# 01_Power.net
KiCad netlist of a schematic drawn in Altium Designer
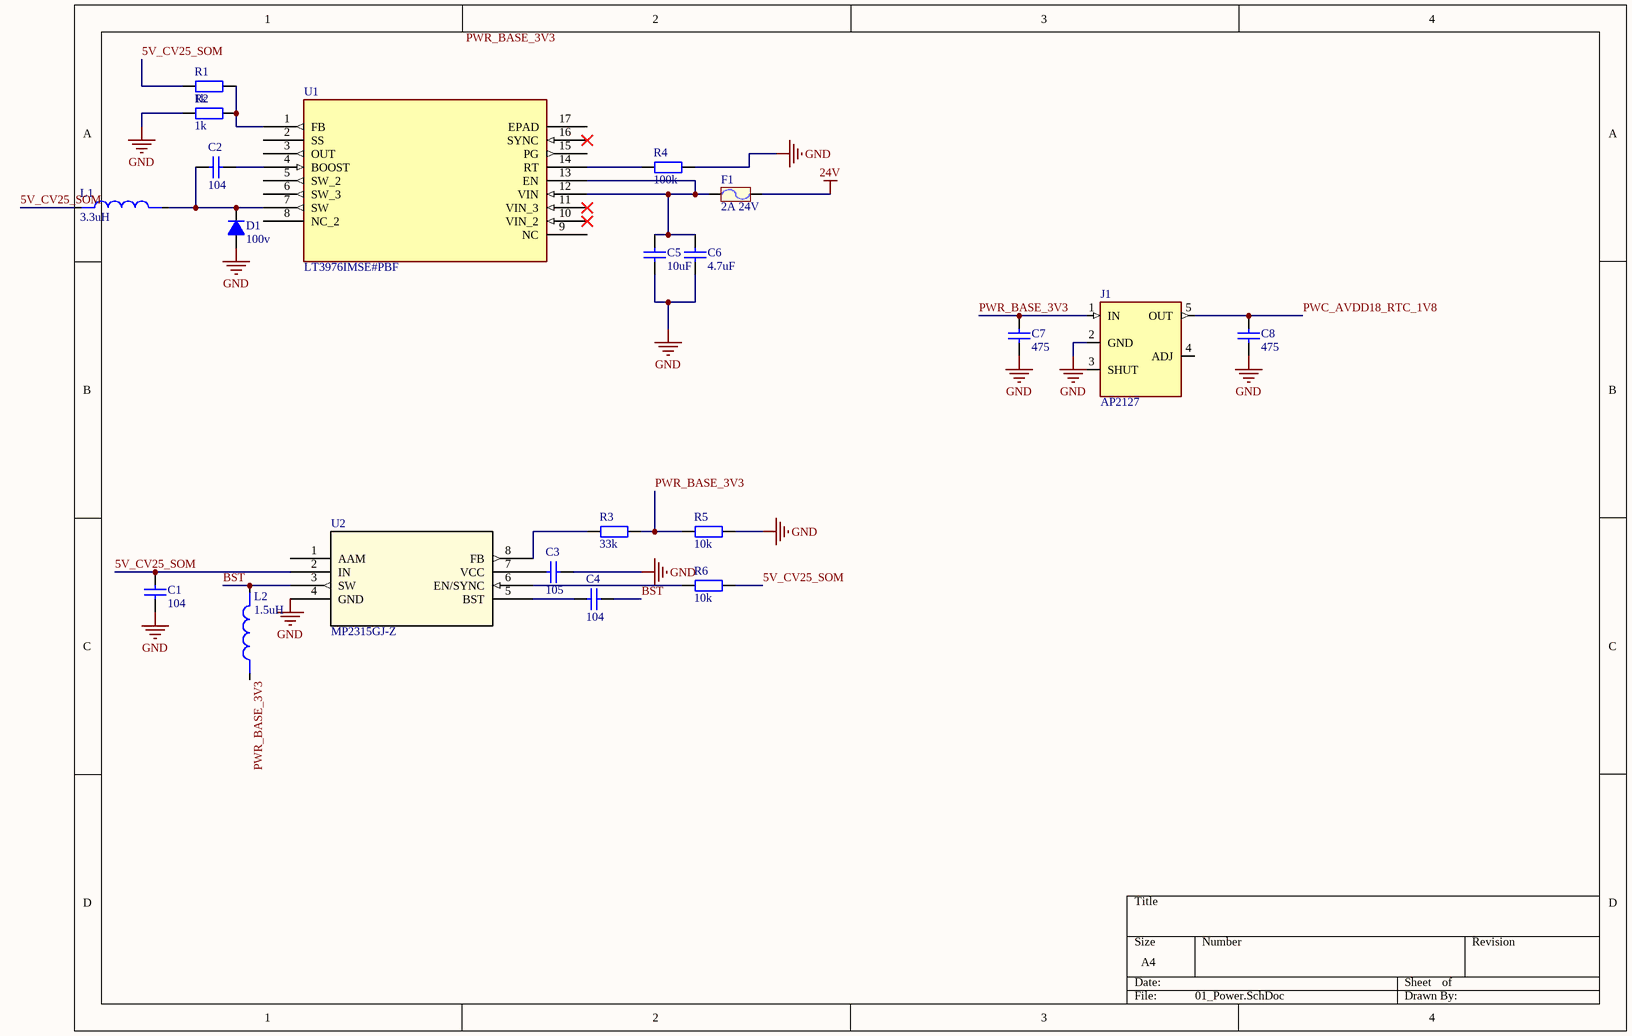
[diagram p0: 01_Power.SchDoc]

(export (version "E")
  (design (tool "Eeschema 10.0.6"))
  (components
    (comp (ref "C1")
      (value "104")
      (footprint "tu 0603")
      (description "Dán")
      (libsource (lib "Altium_Lib_by_KhueNguyenCreator") (part "Tu 0603 104 50V 10%"))
    )
    (comp (ref "C2")
      (value "104")
      (footprint "tu 0603")
      (description "Dán")
      (libsource (lib "Altium_Lib_by_KhueNguyenCreator") (part "Tu 0603 104 50V 10%"))
    )
    (comp (ref "C3")
      (value "105")
      (footprint "tu 0603")
      (description "Dán")
      (libsource (lib "Altium_Lib_by_KhueNguyenCreator") (part "Tu 0603 105 16V 20%"))
    )
    (comp (ref "C4")
      (value "104")
      (footprint "tu 0603")
      (description "Dán")
      (libsource (lib "Altium_Lib_by_KhueNguyenCreator") (part "Tu 0603 104 50V 10%"))
    )
    (comp (ref "C5")
      (value "10uF")
      (footprint "tu 0603")
      (description "Dán")
      (libsource (lib "Altium_Lib_by_KhueNguyenCreator") (part "Tu 0603 470pF 50V 10%"))
    )
    (comp (ref "C6")
      (value "4.7uF")
      (footprint "tu 0603")
      (description "Dán")
      (libsource (lib "Altium_Lib_by_KhueNguyenCreator") (part "Tu 0603 470pF 50V 10%"))
    )
    (comp (ref "C7")
      (value "475")
      (footprint "tu 0805")
      (description "Dán")
      (libsource (lib "Altium_Lib_by_KhueNguyenCreator") (part "Tu 0805 475 25V 20%"))
    )
    (comp (ref "C8")
      (value "475")
      (footprint "tu 0805")
      (description "Dán")
      (libsource (lib "Altium_Lib_by_KhueNguyenCreator") (part "Tu 0805 475 25V 20%"))
    )
    (comp (ref "D1")
      (value "100v")
      (footprint "DIODE 1A")
      (description "Cắm")
      (libsource (lib "Altium_Lib_by_KhueNguyenCreator") (part "Diode 1N4007"))
    )
    (comp (ref "F1")
      (value "2A 24V")
      (footprint "Cau chi tu phuc hoi 2A 24V SMD1812")
      (description "2A 24V SMD1812")
      (libsource (lib "Altium_Lib_by_KhueNguyenCreator") (part "Cau chi tu phuc hoi 2A 24V SMD1812"))
    )
    (comp (ref "J1")
      (value "AP2127")
      (footprint "AP2127K-3.3")
      (description "LDO Regulator Pos 1.8V 0.4A 5-Pin SOT-23 T/R / IC REG LDO 1.8V 0.3A SOT23-5")
      (fields (field (name "MF") "Diodes Incorporated"))
      (libsource (lib "AP2127") (part "AP2127"))
    )
    (comp (ref "L1")
      (value "3.3uH")
      (footprint "CUON CAM SMD 0530")
      (description "SMD 0530")
      (fields (field (name "MP") "FDV0530-H-1R5M=P3"))
      (libsource (lib "Altium_Lib_by_KhueNguyenCreator") (part "Cuon Cam SMD 0530"))
    )
    (comp (ref "L2")
      (value "1.5uH")
      (footprint "CUON CAM SMD 0530")
      (description "SMD 0530")
      (fields (field (name "MP") "FDV0530-H-1R5M=P3"))
      (libsource (lib "Altium_Lib_by_KhueNguyenCreator") (part "Cuon Cam SMD 0530"))
    )
    (comp (ref "R1")
      (value "1k")
      (footprint "tro smd 0603")
      (description "Dán")
      (libsource (lib "Altium_Lib_by_KhueNguyenCreator") (part "Tro 0603 1% 1k"))
    )
    (comp (ref "R2")
      (value "1k")
      (footprint "tro smd 0603")
      (description "Dán")
      (libsource (lib "Altium_Lib_by_KhueNguyenCreator") (part "Tro 0603 1% 1k"))
    )
    (comp (ref "R3")
      (value "33k")
      (footprint "Tro smd 0603")
      (description "Dán")
      (libsource (lib "Altium_Lib_by_KhueNguyenCreator") (part "Tro 0603 1% 33k"))
    )
    (comp (ref "R4")
      (value "100k")
      (footprint "tro smd 0805")
      (description "Dán")
      (libsource (lib "Altium_Lib_by_KhueNguyenCreator") (part "Tro 0805 5% 100k"))
    )
    (comp (ref "R5")
      (value "10k")
      (footprint "tro smd 0603")
      (description "Dán")
      (libsource (lib "Altium_Lib_by_KhueNguyenCreator") (part "Tro 0603 1% 10k"))
    )
    (comp (ref "R6")
      (value "10k")
      (footprint "tro smd 0603")
      (description "Dán")
      (libsource (lib "Altium_Lib_by_KhueNguyenCreator") (part "Tro 0603 1% 10k"))
    )
    (comp (ref "U1")
      (value "LT3976IMSE#PBF")
      (footprint "MSOP-16_MSE")
      (description "40V, 5A, 2MHz Step-Down Switching Regulator with 3.3渭A Quiescent Current")
      (fields (field (name "MF") "Analog Devices"))
      (libsource (lib "LT3976IMSE_PBF") (part "LT3976IMSE#PBF"))
    )
    (comp (ref "U2")
      (value "MP2315GJ-Z")
      (footprint "TSOT23-8_MPS")
      (fields (field (name "COPYRIGHT") "Copyright (C) 2026 Ultra Librarian. All rights reserved."))
      (libsource (lib "MP2315GJ-Z") (part "MP2315GJ-Z"))
    )
  )
  (nets
    (net (code "1") (name "/5V_CV25_SOM") (class "Default")
      (node (ref "C1") (pin "1") (pinfunction "1_1") (pintype "passive"))
      (node (ref "L1") (pin "1") (pinfunction "1_1") (pintype "passive"))
      (node (ref "R1") (pin "1") (pinfunction "1_1") (pintype "passive"))
      (node (ref "R6") (pin "2") (pinfunction "2_2") (pintype "passive"))
      (node (ref "U2") (pin "2") (pinfunction "IN_2") (pintype "power_in"))
    )
    (net (code "2") (name "/BST") (class "Default")
      (node (ref "C4") (pin "1") (pinfunction "1_1") (pintype "passive"))
      (node (ref "L2") (pin "2") (pinfunction "2_2") (pintype "passive"))
      (node (ref "U2") (pin "3") (pinfunction "SW_3") (pintype "output"))
    )
    (net (code "3") (name "/PWC_AVDD18_RTC_1V8") (class "Default")
      (node (ref "C8") (pin "1") (pinfunction "1_1") (pintype "passive"))
      (node (ref "J1") (pin "5") (pinfunction "OUT_5") (pintype "output"))
    )
    (net (code "4") (name "/PWR_BASE_3V3") (class "Default")
      (node (ref "C7") (pin "1") (pinfunction "1_1") (pintype "passive"))
      (node (ref "J1") (pin "1") (pinfunction "IN_1") (pintype "input"))
      (node (ref "L2") (pin "1") (pinfunction "1_1") (pintype "passive"))
      (node (ref "R3") (pin "2") (pinfunction "2_2") (pintype "passive"))
      (node (ref "R5") (pin "1") (pinfunction "1_1") (pintype "passive"))
    )
    (net (code "5") (name "24V") (class "Default")
      (node (ref "F1") (pin "2") (pinfunction "2_2") (pintype "passive"))
    )
    (net (code "6") (name "GND") (class "Default")
      (node (ref "C1") (pin "2") (pinfunction "2_2") (pintype "passive"))
      (node (ref "C3") (pin "1") (pinfunction "1_1") (pintype "passive"))
      (node (ref "C5") (pin "1") (pinfunction "1_1") (pintype "passive"))
      (node (ref "C6") (pin "1") (pinfunction "1_1") (pintype "passive"))
      (node (ref "C7") (pin "2") (pinfunction "2_2") (pintype "passive"))
      (node (ref "C8") (pin "2") (pinfunction "2_2") (pintype "passive"))
      (node (ref "D1") (pin "1") (pinfunction "A_1") (pintype "passive"))
      (node (ref "J1") (pin "2") (pinfunction "GND_2") (pintype "power_in"))
      (node (ref "R2") (pin "1") (pinfunction "1_1") (pintype "passive"))
      (node (ref "R4") (pin "2") (pinfunction "2_2") (pintype "passive"))
      (node (ref "R5") (pin "2") (pinfunction "2_2") (pintype "passive"))
      (node (ref "U2") (pin "4") (pinfunction "GND_4") (pintype "power_in"))
    )
    (net (code "7") (name "Net-(D1-K)") (class "Default")
      (node (ref "C2") (pin "2") (pinfunction "2_2") (pintype "passive"))
      (node (ref "D1") (pin "2") (pinfunction "K_2") (pintype "passive"))
      (node (ref "L1") (pin "2") (pinfunction "2_2") (pintype "passive"))
      (node (ref "U1") (pin "7") (pinfunction "SW_7") (pintype "output"))
    )
    (net (code "8") (name "Net-(U1-BOOST)") (class "Default")
      (node (ref "C2") (pin "1") (pinfunction "1_1") (pintype "passive"))
      (node (ref "U1") (pin "4") (pinfunction "BOOST_4") (pintype "input"))
    )
    (net (code "9") (name "Net-(U1-EN)") (class "Default")
      (node (ref "C5") (pin "2") (pinfunction "2_2") (pintype "passive"))
      (node (ref "C6") (pin "2") (pinfunction "2_2") (pintype "passive"))
      (node (ref "F1") (pin "1") (pinfunction "1_1") (pintype "passive"))
      (node (ref "U1") (pin "12") (pinfunction "VIN_12") (pintype "input"))
      (node (ref "U1") (pin "13") (pinfunction "EN_13") (pintype "passive"))
    )
    (net (code "10") (name "Net-(U1-FB)") (class "Default")
      (node (ref "R1") (pin "2") (pinfunction "2_2") (pintype "passive"))
      (node (ref "R2") (pin "2") (pinfunction "2_2") (pintype "passive"))
      (node (ref "U1") (pin "1") (pinfunction "FB_1") (pintype "output"))
    )
    (net (code "11") (name "Net-(U1-RT)") (class "Default")
      (node (ref "R4") (pin "1") (pinfunction "1_1") (pintype "passive"))
      (node (ref "U1") (pin "14") (pinfunction "RT_14") (pintype "passive"))
    )
    (net (code "12") (name "Net-(U2-BST)") (class "Default")
      (node (ref "C4") (pin "2") (pinfunction "2_2") (pintype "passive"))
      (node (ref "U2") (pin "5") (pinfunction "BST_5") (pintype "passive"))
    )
    (net (code "13") (name "Net-(U2-EN{slash}SYNC)") (class "Default")
      (node (ref "R6") (pin "1") (pinfunction "1_1") (pintype "passive"))
      (node (ref "U2") (pin "6") (pinfunction "EN/SYNC_6") (pintype "input"))
    )
    (net (code "14") (name "Net-(U2-FB)") (class "Default")
      (node (ref "R3") (pin "1") (pinfunction "1_1") (pintype "passive"))
      (node (ref "U2") (pin "8") (pinfunction "FB_8") (pintype "output"))
    )
    (net (code "15") (name "Net-(U2-VCC)") (class "Default")
      (node (ref "C3") (pin "2") (pinfunction "2_2") (pintype "passive"))
      (node (ref "U2") (pin "7") (pinfunction "VCC_7") (pintype "power_in"))
    )
    (net (code "16") (name "unconnected-(J1-ADJ-Pad4)") (class "Default")
      (node (ref "J1") (pin "4") (pinfunction "ADJ_4") (pintype "bidirectional"))
    )
    (net (code "17") (name "unconnected-(J1-SHUT-Pad3)") (class "Default")
      (node (ref "J1") (pin "3") (pinfunction "SHUT_3") (pintype "bidirectional"))
    )
    (net (code "18") (name "unconnected-(U1-EPAD-Pad17)") (class "Default")
      (node (ref "U1") (pin "17") (pinfunction "EPAD_17") (pintype "passive"))
    )
    (net (code "19") (name "unconnected-(U1-NC-Pad9)") (class "Default")
      (node (ref "U1") (pin "9") (pinfunction "NC_9") (pintype "passive"))
    )
    (net (code "20") (name "unconnected-(U1-NC_2-Pad8)") (class "Default")
      (node (ref "U1") (pin "8") (pinfunction "NC_2_8") (pintype "passive"))
    )
    (net (code "21") (name "unconnected-(U1-OUT-Pad3)") (class "Default")
      (node (ref "U1") (pin "3") (pinfunction "OUT_3") (pintype "output"))
    )
    (net (code "22") (name "unconnected-(U1-PG-Pad15)") (class "Default")
      (node (ref "U1") (pin "15") (pinfunction "PG_15") (pintype "output"))
    )
    (net (code "23") (name "unconnected-(U1-SS-Pad2)") (class "Default")
      (node (ref "U1") (pin "2") (pinfunction "SS_2") (pintype "passive"))
    )
    (net (code "24") (name "unconnected-(U1-SW_2-Pad5)") (class "Default")
      (node (ref "U1") (pin "5") (pinfunction "SW_2_5") (pintype "output"))
    )
    (net (code "25") (name "unconnected-(U1-SW_3-Pad6)") (class "Default")
      (node (ref "U1") (pin "6") (pinfunction "SW_3_6") (pintype "output"))
    )
    (net (code "26") (name "unconnected-(U1-SYNC-Pad16)") (class "Default")
      (node (ref "U1") (pin "16") (pinfunction "SYNC_16") (pintype "input+no_connect"))
    )
    (net (code "27") (name "unconnected-(U1-VIN_2-Pad10)") (class "Default")
      (node (ref "U1") (pin "10") (pinfunction "VIN_2_10") (pintype "input+no_connect"))
    )
    (net (code "28") (name "unconnected-(U1-VIN_3-Pad11)") (class "Default")
      (node (ref "U1") (pin "11") (pinfunction "VIN_3_11") (pintype "input+no_connect"))
    )
    (net (code "29") (name "unconnected-(U2-AAM-Pad1)") (class "Default")
      (node (ref "U2") (pin "1") (pinfunction "AAM_1") (pintype "passive"))
    )
  )
)
